# Newmark_Controller.net
KiCad netlist of a schematic drawn in EAGLE
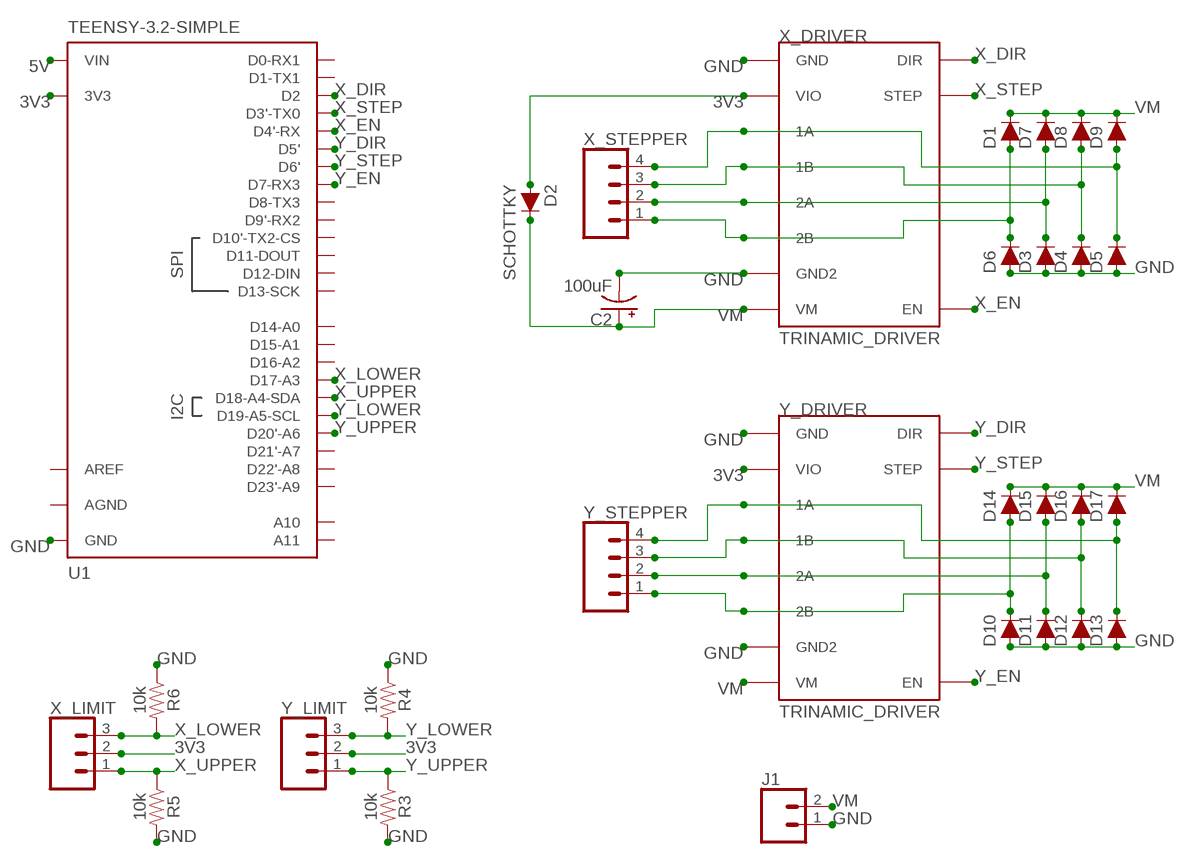
[diagram p0: schematic, sheet 1]

(export (version "E")
  (design (tool "Eeschema 10.0.6"))
  (components
    (comp (ref "C2")
      (value "100uF")
      (footprint "eagle-import:CPOL-RADIAL-2.5MM-6.5MM")
      (libsource (lib "eagle-import") (part "100UF-POLAR-RADIAL-2.5MM-25V-20%"))
    )
    (comp (ref "D1")
      (value "DIODE-1N4148")
      (footprint "eagle-import:DIODE-1N4148")
      (libsource (lib "eagle-import") (part "DIODE-1N4148"))
    )
    (comp (ref "D2")
      (value "SCHOTTKY")
      (footprint "eagle-import:DIODE-1N4148")
      (libsource (lib "eagle-import") (part "DIODE-1N4148"))
    )
    (comp (ref "D3")
      (value "DIODE-1N4148")
      (footprint "eagle-import:DIODE-1N4148")
      (libsource (lib "eagle-import") (part "DIODE-1N4148"))
    )
    (comp (ref "D4")
      (value "DIODE-1N4148")
      (footprint "eagle-import:DIODE-1N4148")
      (libsource (lib "eagle-import") (part "DIODE-1N4148"))
    )
    (comp (ref "D5")
      (value "DIODE-1N4148")
      (footprint "eagle-import:DIODE-1N4148")
      (libsource (lib "eagle-import") (part "DIODE-1N4148"))
    )
    (comp (ref "D6")
      (value "DIODE-1N4148")
      (footprint "eagle-import:DIODE-1N4148")
      (libsource (lib "eagle-import") (part "DIODE-1N4148"))
    )
    (comp (ref "D7")
      (value "DIODE-1N4148")
      (footprint "eagle-import:DIODE-1N4148")
      (libsource (lib "eagle-import") (part "DIODE-1N4148"))
    )
    (comp (ref "D8")
      (value "DIODE-1N4148")
      (footprint "eagle-import:DIODE-1N4148")
      (libsource (lib "eagle-import") (part "DIODE-1N4148"))
    )
    (comp (ref "D9")
      (value "DIODE-1N4148")
      (footprint "eagle-import:DIODE-1N4148")
      (libsource (lib "eagle-import") (part "DIODE-1N4148"))
    )
    (comp (ref "D10")
      (value "DIODE-1N4148")
      (footprint "eagle-import:DIODE-1N4148")
      (libsource (lib "eagle-import") (part "DIODE-1N4148"))
    )
    (comp (ref "D11")
      (value "DIODE-1N4148")
      (footprint "eagle-import:DIODE-1N4148")
      (libsource (lib "eagle-import") (part "DIODE-1N4148"))
    )
    (comp (ref "D12")
      (value "DIODE-1N4148")
      (footprint "eagle-import:DIODE-1N4148")
      (libsource (lib "eagle-import") (part "DIODE-1N4148"))
    )
    (comp (ref "D13")
      (value "DIODE-1N4148")
      (footprint "eagle-import:DIODE-1N4148")
      (libsource (lib "eagle-import") (part "DIODE-1N4148"))
    )
    (comp (ref "D14")
      (value "DIODE-1N4148")
      (footprint "eagle-import:DIODE-1N4148")
      (libsource (lib "eagle-import") (part "DIODE-1N4148"))
    )
    (comp (ref "D15")
      (value "DIODE-1N4148")
      (footprint "eagle-import:DIODE-1N4148")
      (libsource (lib "eagle-import") (part "DIODE-1N4148"))
    )
    (comp (ref "D16")
      (value "DIODE-1N4148")
      (footprint "eagle-import:DIODE-1N4148")
      (libsource (lib "eagle-import") (part "DIODE-1N4148"))
    )
    (comp (ref "D17")
      (value "DIODE-1N4148")
      (footprint "eagle-import:DIODE-1N4148")
      (libsource (lib "eagle-import") (part "DIODE-1N4148"))
    )
    (comp (ref "J1")
      (value "CONN_023.5MM")
      (footprint "eagle-import:SCREWTERMINAL-3.5MM-2")
      (libsource (lib "eagle-import") (part "CONN_023.5MM"))
    )
    (comp (ref "R3")
      (value "10k")
      (footprint "eagle-import:AXIAL-0.3")
      (libsource (lib "eagle-import") (part "10KOHM-HORIZ-1/6W-5%"))
    )
    (comp (ref "R4")
      (value "10k")
      (footprint "eagle-import:AXIAL-0.3")
      (libsource (lib "eagle-import") (part "10KOHM-HORIZ-1/6W-5%"))
    )
    (comp (ref "R5")
      (value "10k")
      (footprint "eagle-import:AXIAL-0.3")
      (libsource (lib "eagle-import") (part "10KOHM-HORIZ-1/6W-5%"))
    )
    (comp (ref "R6")
      (value "10k")
      (footprint "eagle-import:AXIAL-0.3")
      (libsource (lib "eagle-import") (part "10KOHM-HORIZ-1/6W-5%"))
    )
    (comp (ref "U1")
      (value "TEENSY-3.2-SIMPLE")
      (footprint "eagle-import:TEENSY-3.2-SIMPLE")
      (libsource (lib "eagle-import") (part "TEENSY-3.2-SIMPLE"))
    )
    (comp (ref "X_DRIVER")
      (value "TRINAMIC_DRIVER")
      (footprint "eagle-import:TRINAMIC_DRIVER")
      (libsource (lib "eagle-import") (part "TRINAMIC_DRIVER"))
    )
    (comp (ref "X_LIMIT")
      (value "CONN_03")
      (footprint "eagle-import:1X03")
      (libsource (lib "eagle-import") (part "CONN_03"))
    )
    (comp (ref "X_STEPPER")
      (value "CONN_04PTH")
      (footprint "eagle-import:1X04")
      (libsource (lib "eagle-import") (part "CONN_04PTH"))
    )
    (comp (ref "Y_DRIVER")
      (value "TRINAMIC_DRIVER")
      (footprint "eagle-import:TRINAMIC_DRIVER")
      (libsource (lib "eagle-import") (part "TRINAMIC_DRIVER"))
    )
    (comp (ref "Y_LIMIT")
      (value "CONN_03")
      (footprint "eagle-import:1X03")
      (libsource (lib "eagle-import") (part "CONN_03"))
    )
    (comp (ref "Y_STEPPER")
      (value "CONN_04PTH")
      (footprint "eagle-import:1X04")
      (libsource (lib "eagle-import") (part "CONN_04PTH"))
    )
  )
  (nets
    (net (code "1") (name "/3V3") (class "Default")
      (node (ref "D2") (pin "A") (pinfunction "A_A") (pintype "passive"))
      (node (ref "U1") (pin "3.3V") (pinfunction "3V3_3.3V") (pintype "power_in"))
      (node (ref "X_DRIVER") (pin "5V") (pinfunction "VIO_5V") (pintype "bidirectional"))
      (node (ref "X_LIMIT") (pin "2") (pinfunction "2_2") (pintype "passive"))
      (node (ref "Y_DRIVER") (pin "5V") (pinfunction "VIO_5V") (pintype "bidirectional"))
      (node (ref "Y_LIMIT") (pin "2") (pinfunction "2_2") (pintype "passive"))
    )
    (net (code "2") (name "/5V") (class "Default")
      (node (ref "U1") (pin "VIN") (pinfunction "VIN_VIN") (pintype "power_in"))
    )
    (net (code "3") (name "/AGND") (class "Default")
      (node (ref "U1") (pin "AGND") (pinfunction "AGND_AGND") (pintype "power_in"))
    )
    (net (code "4") (name "/AREF") (class "Default")
      (node (ref "U1") (pin "AREF") (pinfunction "AREF_AREF") (pintype "power_in"))
    )
    (net (code "5") (name "/GND") (class "Default")
      (node (ref "C2") (pin "2") (pinfunction "-_2") (pintype "passive"))
      (node (ref "D10") (pin "A") (pinfunction "A_A") (pintype "passive"))
      (node (ref "D11") (pin "A") (pinfunction "A_A") (pintype "passive"))
      (node (ref "D12") (pin "A") (pinfunction "A_A") (pintype "passive"))
      (node (ref "D13") (pin "A") (pinfunction "A_A") (pintype "passive"))
      (node (ref "D3") (pin "A") (pinfunction "A_A") (pintype "passive"))
      (node (ref "D4") (pin "A") (pinfunction "A_A") (pintype "passive"))
      (node (ref "D5") (pin "A") (pinfunction "A_A") (pintype "passive"))
      (node (ref "D6") (pin "A") (pinfunction "A_A") (pintype "passive"))
      (node (ref "J1") (pin "1") (pinfunction "1_1") (pintype "passive"))
      (node (ref "R3") (pin "P$2") (pinfunction "2_P$2") (pintype "passive"))
      (node (ref "R4") (pin "P$1") (pinfunction "1_P$1") (pintype "passive"))
      (node (ref "R5") (pin "P$2") (pinfunction "2_P$2") (pintype "passive"))
      (node (ref "R6") (pin "P$1") (pinfunction "1_P$1") (pintype "passive"))
      (node (ref "U1") (pin "GND") (pinfunction "GND_GND") (pintype "power_in"))
      (node (ref "X_DRIVER") (pin "GND") (pinfunction "GND_GND") (pintype "bidirectional"))
      (node (ref "X_DRIVER") (pin "GND2") (pinfunction "GND2_GND2") (pintype "bidirectional"))
      (node (ref "Y_DRIVER") (pin "GND") (pinfunction "GND_GND") (pintype "bidirectional"))
      (node (ref "Y_DRIVER") (pin "GND2") (pinfunction "GND2_GND2") (pintype "bidirectional"))
    )
    (net (code "6") (name "/VM") (class "Default")
      (node (ref "C2") (pin "1") (pinfunction "+_1") (pintype "passive"))
      (node (ref "D1") (pin "C") (pinfunction "C_C") (pintype "passive"))
      (node (ref "D14") (pin "C") (pinfunction "C_C") (pintype "passive"))
      (node (ref "D15") (pin "C") (pinfunction "C_C") (pintype "passive"))
      (node (ref "D16") (pin "C") (pinfunction "C_C") (pintype "passive"))
      (node (ref "D17") (pin "C") (pinfunction "C_C") (pintype "passive"))
      (node (ref "D2") (pin "C") (pinfunction "C_C") (pintype "passive"))
      (node (ref "D7") (pin "C") (pinfunction "C_C") (pintype "passive"))
      (node (ref "D8") (pin "C") (pinfunction "C_C") (pintype "passive"))
      (node (ref "D9") (pin "C") (pinfunction "C_C") (pintype "passive"))
      (node (ref "J1") (pin "2") (pinfunction "2_2") (pintype "passive"))
      (node (ref "X_DRIVER") (pin "VM") (pinfunction "VM_VM") (pintype "bidirectional"))
      (node (ref "Y_DRIVER") (pin "VM") (pinfunction "VM_VM") (pintype "bidirectional"))
    )
    (net (code "7") (name "/X_DIR") (class "Default")
      (node (ref "U1") (pin "2") (pinfunction "D2_2") (pintype "bidirectional"))
      (node (ref "X_DRIVER") (pin "DIR") (pinfunction "DIR_DIR") (pintype "bidirectional"))
    )
    (net (code "8") (name "/X_EN") (class "Default")
      (node (ref "U1") (pin "4") (pinfunction "D4'-RX_4") (pintype "bidirectional"))
      (node (ref "X_DRIVER") (pin "EN") (pinfunction "EN_EN") (pintype "bidirectional"))
    )
    (net (code "9") (name "/X_LOWER") (class "Default")
      (node (ref "R6") (pin "P$2") (pinfunction "2_P$2") (pintype "passive"))
      (node (ref "U1") (pin "17") (pinfunction "D17-A3_17") (pintype "bidirectional"))
      (node (ref "X_LIMIT") (pin "3") (pinfunction "3_3") (pintype "passive"))
    )
    (net (code "10") (name "/X_STEP") (class "Default")
      (node (ref "U1") (pin "3") (pinfunction "D3'-TX0_3") (pintype "bidirectional"))
      (node (ref "X_DRIVER") (pin "STEP") (pinfunction "STEP_STEP") (pintype "bidirectional"))
    )
    (net (code "11") (name "/X_UPPER") (class "Default")
      (node (ref "R5") (pin "P$1") (pinfunction "1_P$1") (pintype "passive"))
      (node (ref "U1") (pin "18") (pinfunction "D18-A4-SDA_18") (pintype "bidirectional"))
      (node (ref "X_LIMIT") (pin "1") (pinfunction "1_1") (pintype "passive"))
    )
    (net (code "12") (name "/Y_DIR") (class "Default")
      (node (ref "U1") (pin "5") (pinfunction "D5'_5") (pintype "bidirectional"))
      (node (ref "Y_DRIVER") (pin "DIR") (pinfunction "DIR_DIR") (pintype "bidirectional"))
    )
    (net (code "13") (name "/Y_EN") (class "Default")
      (node (ref "U1") (pin "7") (pinfunction "D7-RX3_7") (pintype "bidirectional"))
      (node (ref "Y_DRIVER") (pin "EN") (pinfunction "EN_EN") (pintype "bidirectional"))
    )
    (net (code "14") (name "/Y_LOWER") (class "Default")
      (node (ref "R4") (pin "P$2") (pinfunction "2_P$2") (pintype "passive"))
      (node (ref "U1") (pin "19") (pinfunction "D19-A5-SCL_19") (pintype "bidirectional"))
      (node (ref "Y_LIMIT") (pin "3") (pinfunction "3_3") (pintype "passive"))
    )
    (net (code "15") (name "/Y_STEP") (class "Default")
      (node (ref "U1") (pin "6") (pinfunction "D6'_6") (pintype "bidirectional"))
      (node (ref "Y_DRIVER") (pin "STEP") (pinfunction "STEP_STEP") (pintype "bidirectional"))
    )
    (net (code "16") (name "/Y_UPPER") (class "Default")
      (node (ref "R3") (pin "P$1") (pinfunction "1_P$1") (pintype "passive"))
      (node (ref "U1") (pin "20") (pinfunction "D20'-A6_20") (pintype "bidirectional"))
      (node (ref "Y_LIMIT") (pin "1") (pinfunction "1_1") (pintype "passive"))
    )
    (net (code "17") (name "Net-(D1-PadA)") (class "Default")
      (node (ref "D1") (pin "A") (pinfunction "A_A") (pintype "passive"))
      (node (ref "D6") (pin "C") (pinfunction "C_C") (pintype "passive"))
      (node (ref "X_DRIVER") (pin "2B") (pinfunction "2B_2B") (pintype "bidirectional"))
      (node (ref "X_STEPPER") (pin "1") (pinfunction "1_1") (pintype "passive"))
    )
    (net (code "18") (name "Net-(D3-PadC)") (class "Default")
      (node (ref "D3") (pin "C") (pinfunction "C_C") (pintype "passive"))
      (node (ref "D7") (pin "A") (pinfunction "A_A") (pintype "passive"))
      (node (ref "X_DRIVER") (pin "2A") (pinfunction "2A_2A") (pintype "bidirectional"))
      (node (ref "X_STEPPER") (pin "2") (pinfunction "2_2") (pintype "passive"))
    )
    (net (code "19") (name "Net-(D4-PadC)") (class "Default")
      (node (ref "D4") (pin "C") (pinfunction "C_C") (pintype "passive"))
      (node (ref "D8") (pin "A") (pinfunction "A_A") (pintype "passive"))
      (node (ref "X_DRIVER") (pin "1B") (pinfunction "1B_1B") (pintype "bidirectional"))
      (node (ref "X_STEPPER") (pin "3") (pinfunction "3_3") (pintype "passive"))
    )
    (net (code "20") (name "Net-(D5-PadC)") (class "Default")
      (node (ref "D5") (pin "C") (pinfunction "C_C") (pintype "passive"))
      (node (ref "D9") (pin "A") (pinfunction "A_A") (pintype "passive"))
      (node (ref "X_DRIVER") (pin "1A") (pinfunction "1A_1A") (pintype "bidirectional"))
      (node (ref "X_STEPPER") (pin "4") (pinfunction "4_4") (pintype "passive"))
    )
    (net (code "21") (name "Net-(D10-PadC)") (class "Default")
      (node (ref "D10") (pin "C") (pinfunction "C_C") (pintype "passive"))
      (node (ref "D14") (pin "A") (pinfunction "A_A") (pintype "passive"))
      (node (ref "Y_DRIVER") (pin "2B") (pinfunction "2B_2B") (pintype "bidirectional"))
      (node (ref "Y_STEPPER") (pin "1") (pinfunction "1_1") (pintype "passive"))
    )
    (net (code "22") (name "Net-(D11-PadC)") (class "Default")
      (node (ref "D11") (pin "C") (pinfunction "C_C") (pintype "passive"))
      (node (ref "D15") (pin "A") (pinfunction "A_A") (pintype "passive"))
      (node (ref "Y_DRIVER") (pin "2A") (pinfunction "2A_2A") (pintype "bidirectional"))
      (node (ref "Y_STEPPER") (pin "2") (pinfunction "2_2") (pintype "passive"))
    )
    (net (code "23") (name "Net-(D12-PadC)") (class "Default")
      (node (ref "D12") (pin "C") (pinfunction "C_C") (pintype "passive"))
      (node (ref "D16") (pin "A") (pinfunction "A_A") (pintype "passive"))
      (node (ref "Y_DRIVER") (pin "1B") (pinfunction "1B_1B") (pintype "bidirectional"))
      (node (ref "Y_STEPPER") (pin "3") (pinfunction "3_3") (pintype "passive"))
    )
    (net (code "24") (name "Net-(D13-PadC)") (class "Default")
      (node (ref "D13") (pin "C") (pinfunction "C_C") (pintype "passive"))
      (node (ref "D17") (pin "A") (pinfunction "A_A") (pintype "passive"))
      (node (ref "Y_DRIVER") (pin "1A") (pinfunction "1A_1A") (pintype "bidirectional"))
      (node (ref "Y_STEPPER") (pin "4") (pinfunction "4_4") (pintype "passive"))
    )
    (net (code "25") (name "unconnected-(U1-D0-RX1-Pad0)") (class "Default")
      (node (ref "U1") (pin "0") (pinfunction "D0-RX1_0") (pintype "bidirectional"))
    )
    (net (code "26") (name "unconnected-(U1-D1-TX1-Pad1)") (class "Default")
      (node (ref "U1") (pin "1") (pinfunction "D1-TX1_1") (pintype "bidirectional"))
    )
    (net (code "27") (name "unconnected-(U1-D8-TX3-Pad8)") (class "Default")
      (node (ref "U1") (pin "8") (pinfunction "D8-TX3_8") (pintype "bidirectional"))
    )
    (net (code "28") (name "unconnected-(U1-D9'-RX2-Pad9)") (class "Default")
      (node (ref "U1") (pin "9") (pinfunction "D9'-RX2_9") (pintype "bidirectional"))
    )
    (net (code "29") (name "unconnected-(U1-D10'-TX2-CS-Pad10)") (class "Default")
      (node (ref "U1") (pin "10") (pinfunction "D10'-TX2-CS_10") (pintype "bidirectional"))
    )
    (net (code "30") (name "unconnected-(U1-D11-DOUT-Pad11)") (class "Default")
      (node (ref "U1") (pin "11") (pinfunction "D11-DOUT_11") (pintype "bidirectional"))
    )
    (net (code "31") (name "unconnected-(U1-D12-DIN-Pad12)") (class "Default")
      (node (ref "U1") (pin "12") (pinfunction "D12-DIN_12") (pintype "bidirectional"))
    )
    (net (code "32") (name "unconnected-(U1-D13-SCK-Pad13)") (class "Default")
      (node (ref "U1") (pin "13") (pinfunction "D13-SCK_13") (pintype "bidirectional"))
    )
    (net (code "33") (name "unconnected-(U1-D14-A0-Pad14)") (class "Default")
      (node (ref "U1") (pin "14") (pinfunction "D14-A0_14") (pintype "bidirectional"))
    )
    (net (code "34") (name "unconnected-(U1-D15-A1-Pad15)") (class "Default")
      (node (ref "U1") (pin "15") (pinfunction "D15-A1_15") (pintype "bidirectional"))
    )
    (net (code "35") (name "unconnected-(U1-D16-A2-Pad16)") (class "Default")
      (node (ref "U1") (pin "16") (pinfunction "D16-A2_16") (pintype "bidirectional"))
    )
    (net (code "36") (name "unconnected-(U1-D21'-A7-Pad21)") (class "Default")
      (node (ref "U1") (pin "21") (pinfunction "D21'-A7_21") (pintype "bidirectional"))
    )
    (net (code "37") (name "unconnected-(U1-D22'-A8-Pad22)") (class "Default")
      (node (ref "U1") (pin "22") (pinfunction "D22'-A8_22") (pintype "bidirectional"))
    )
    (net (code "38") (name "unconnected-(U1-D23'-A9-Pad23)") (class "Default")
      (node (ref "U1") (pin "23") (pinfunction "D23'-A9_23") (pintype "bidirectional"))
    )
    (net (code "39") (name "unconnected-(U1-PadA10)") (class "Default")
      (node (ref "U1") (pin "A10") (pinfunction "A10_A10") (pintype "bidirectional"))
    )
    (net (code "40") (name "unconnected-(U1-PadA11)") (class "Default")
      (node (ref "U1") (pin "A11") (pinfunction "A11_A11") (pintype "bidirectional"))
    )
  )
)
